# THS3201.net
KiCad netlist of a schematic drawn in Altium Designer
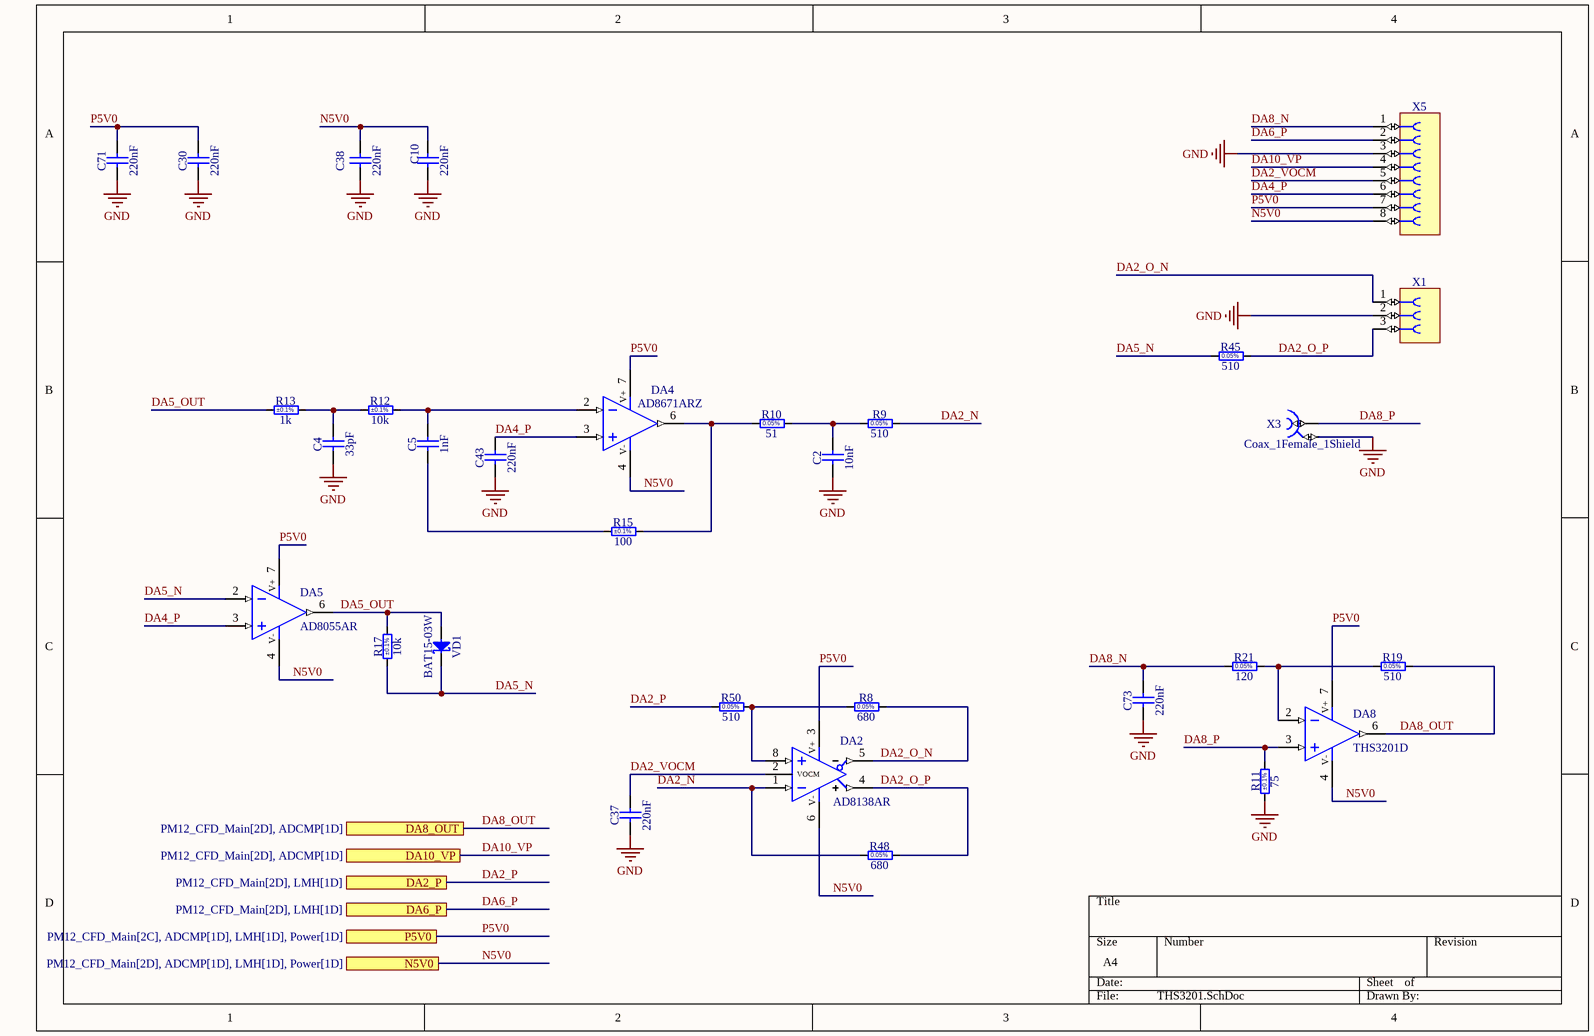
[diagram p0: THS3201.SchDoc]

(export (version "E")
  (design (tool "Eeschema 10.0.6"))
  (components
    (comp (ref "C2")
      (value "10nF")
      (footprint "CAPC2012X135N")
      (description "Non-polarised capacitor")
      (fields
        (field (name "PART NUMBER") "CC0805_10NF_50V_2%_C0G")
        (field (name "VOLTAGE") "50V")
        (field (name "AUTHOR") "CERN DEM HF")
      )
      (libsource (lib "Capacitors") (part "Capacitor - non polarized"))
    )
    (comp (ref "C4")
      (value "33pF")
      (footprint "CAPC2013X115N")
      (description "Non-polarised capacitor")
      (fields
        (field (name "PART NUMBER") "CC0805_33PF_200V_1%_NP0")
        (field (name "VOLTAGE") "200V")
        (field (name "AUTHOR") "CERN DEM HF")
      )
      (libsource (lib "Capacitors") (part "Capacitor - non polarized"))
    )
    (comp (ref "C5")
      (value "1nF")
      (footprint "CAPC2013X100N")
      (description "Non-polarised capacitor")
      (fields
        (field (name "PART NUMBER") "CC0805_1NF_25V_1%_C0G")
        (field (name "VOLTAGE") "25V")
        (field (name "AUTHOR") "CERN DEM JLC")
      )
      (libsource (lib "Capacitors") (part "Capacitor - non polarized"))
    )
    (comp (ref "C10")
      (value "220nF")
      (footprint "CAPC2012X135N")
      (description "Non-polarised capacitor")
      (fields
        (field (name "PART NUMBER") "CC0805_220NF_50V_10%_X7R")
        (field (name "VOLTAGE") "50V")
        (field (name "AUTHOR") "CERN DEM JLC")
      )
      (libsource (lib "Capacitors") (part "Capacitor - non polarized"))
    )
    (comp (ref "C30")
      (value "220nF")
      (footprint "CAPC2012X135N")
      (description "Non-polarised capacitor")
      (fields
        (field (name "PART NUMBER") "CC0805_220NF_50V_10%_X7R")
        (field (name "VOLTAGE") "50V")
        (field (name "AUTHOR") "CERN DEM JLC")
      )
      (libsource (lib "Capacitors") (part "Capacitor - non polarized"))
    )
    (comp (ref "C37")
      (value "220nF")
      (footprint "CAPC2012X135N")
      (description "Non-polarised capacitor")
      (fields
        (field (name "PART NUMBER") "CC0805_220NF_50V_10%_X7R")
        (field (name "VOLTAGE") "50V")
        (field (name "AUTHOR") "CERN DEM JLC")
      )
      (libsource (lib "Capacitors") (part "Capacitor - non polarized"))
    )
    (comp (ref "C38")
      (value "220nF")
      (footprint "CAPC2012X135N")
      (description "Non-polarised capacitor")
      (fields
        (field (name "PART NUMBER") "CC0805_220NF_50V_10%_X7R")
        (field (name "VOLTAGE") "50V")
        (field (name "AUTHOR") "CERN DEM JLC")
      )
      (libsource (lib "Capacitors") (part "Capacitor - non polarized"))
    )
    (comp (ref "C43")
      (value "220nF")
      (footprint "CAPC2012X135N")
      (description "Non-polarised capacitor")
      (fields
        (field (name "PART NUMBER") "CC0805_220NF_50V_10%_X7R")
        (field (name "VOLTAGE") "50V")
        (field (name "AUTHOR") "CERN DEM JLC")
      )
      (libsource (lib "Capacitors") (part "Capacitor - non polarized"))
    )
    (comp (ref "C71")
      (value "220nF")
      (footprint "CAPC2012X135N")
      (description "Non-polarised capacitor")
      (fields
        (field (name "PART NUMBER") "CC0805_220NF_50V_10%_X7R")
        (field (name "VOLTAGE") "50V")
        (field (name "AUTHOR") "CERN DEM JLC")
      )
      (libsource (lib "Capacitors") (part "Capacitor - non polarized"))
    )
    (comp (ref "C73")
      (value "220nF")
      (footprint "CAPC2012X135N")
      (description "Non-polarised capacitor")
      (fields
        (field (name "PART NUMBER") "CC0805_220NF_50V_10%_X7R")
        (field (name "VOLTAGE") "50V")
        (field (name "AUTHOR") "CERN DEM JLC")
      )
      (libsource (lib "Capacitors") (part "Capacitor - non polarized"))
    )
    (comp (ref "DA2")
      (value "AD8138AR")
      (footprint "SOIC127P600X175-8N")
      (description "Differential Amplifier")
      (fields (field (name "MANUFACTURER") "ANALOG DEVICES") (field (name "AUTHOR") "CERN DEM JLC"))
      (libsource (lib "ICs And Semiconductors") (part "Differential Amplifier Type1"))
    )
    (comp (ref "DA4")
      (value "AD8671ARZ")
      (footprint "SOIC127P600X175-8N")
      (description "Operational Amplifier")
      (fields
        (field (name "MANUFACTURER") "ANALOG DEVICES")
        (field (name "MANUFACTURER PART NUMBER") "AD8671AR")
        (field (name "AUTHOR") "CERN DEM JLC")
      )
      (libsource (lib "ICs And Semiconductors") (part "Operational Amplifier Type1"))
    )
    (comp (ref "DA5")
      (value "AD8055AR")
      (footprint "SOIC127P600X175-8N")
      (description "Operational Amplifier")
      (fields (field (name "MANUFACTURER") "ANALOG DEVICES") (field (name "AUTHOR") "CERN DEM HF"))
      (libsource (lib "ICs And Semiconductors") (part "Operational Amplifier Type1"))
    )
    (comp (ref "DA8")
      (value "THS3201D")
      (footprint "SOIC127P600X175-8N")
      (description "Operational Amplifier")
      (fields (field (name "MANUFACTURER") "TEXAS INSTRUMENTS") (field (name "AUTHOR") "CERN DEM HF"))
      (libsource (lib "ICs And Semiconductors") (part "Operational Amplifier Type1"))
    )
    (comp (ref "R8")
      (value "680")
      (footprint "RESC2012X60N")
      (description "Resistor - 0.05%")
      (fields
        (field (name "PART NUMBER") "R0805_680R_0.05%_0.125W_10PPM")
        (field (name "POWER") "0.1W")
        (field (name "AUTHOR") "CERN DEM HF")
      )
      (libsource (lib "Resistors") (part "Resistor - 0.05%"))
    )
    (comp (ref "R9")
      (value "510")
      (footprint "RESC1608X55N")
      (description "Resistor - 0.05%")
      (fields
        (field (name "PART NUMBER") "R0603_510R_0.1%_0.1W_10PPM")
        (field (name "POWER") "0.1W")
        (field (name "AUTHOR") "CERN DEM HF")
      )
      (libsource (lib "Resistors") (part "Resistor - 0.05%"))
    )
    (comp (ref "R10")
      (value "51")
      (footprint "RESC2012X60N")
      (description "Resistor - 0.05%")
      (fields
        (field (name "PART NUMBER") "R0805_51R_0.05%_0.125W_10PPM")
        (field (name "POWER") "0.1W")
        (field (name "AUTHOR") "CERN DEM HF")
      )
      (libsource (lib "Resistors") (part "Resistor - 0.05%"))
    )
    (comp (ref "R11")
      (value "75")
      (footprint "RESC1608X55N")
      (description "Resistor - 0.1%")
      (fields
        (field (name "TOLERANCE") "±0.1%")
        (field (name "PART NUMBER") "R0603_75R_0.1%_0.063W_10PPM")
        (field (name "POWER") "0.063W")
        (field (name "AUTHOR") "CERN DEM JLC")
      )
      (libsource (lib "Resistors") (part "Resistor - 0.1%"))
    )
    (comp (ref "R12")
      (value "10k")
      (footprint "RESC2012X60N")
      (description "Resistor - 0.1%")
      (fields
        (field (name "TOLERANCE") "±0.1%")
        (field (name "PART NUMBER") "R0805_10K_0.1%_0.1W_10PPM")
        (field (name "POWER") "0.1W")
        (field (name "AUTHOR") "CERN DEM JLC")
      )
      (libsource (lib "Resistors") (part "Resistor - 0.1%"))
    )
    (comp (ref "R13")
      (value "1k")
      (footprint "RESC2012X60N")
      (description "Resistor - 0.1%")
      (fields
        (field (name "TOLERANCE") "±0.1%")
        (field (name "PART NUMBER") "R0805_1K_0.1%_0.1W_10PPM")
        (field (name "POWER") "0.1W")
        (field (name "AUTHOR") "CERN DEM JLC")
      )
      (libsource (lib "Resistors") (part "Resistor - 0.1%"))
    )
    (comp (ref "R15")
      (value "100")
      (footprint "RESC2012X60N")
      (description "Resistor - 0.1%")
      (fields
        (field (name "TOLERANCE") "±0.1%")
        (field (name "PART NUMBER") "R0805_100R_0.1%_0.1W_10PPM")
        (field (name "POWER") "0.1W")
        (field (name "AUTHOR") "CERN DEM JLC")
      )
      (libsource (lib "Resistors") (part "Resistor - 0.1%"))
    )
    (comp (ref "R17")
      (value "10k")
      (footprint "RESC2012X60N")
      (description "Resistor - 0.1%")
      (fields
        (field (name "TOLERANCE") "±0.1%")
        (field (name "PART NUMBER") "R0805_10K_0.1%_0.1W_10PPM")
        (field (name "POWER") "0.1W")
        (field (name "AUTHOR") "CERN DEM JLC")
      )
      (libsource (lib "Resistors") (part "Resistor - 0.1%"))
    )
    (comp (ref "R19")
      (value "510")
      (footprint "RESC1608X55N")
      (description "Resistor - 0.05%")
      (fields
        (field (name "PART NUMBER") "R0603_510R_0.1%_0.1W_10PPM")
        (field (name "POWER") "0.1W")
        (field (name "AUTHOR") "CERN DEM HF")
      )
      (libsource (lib "Resistors") (part "Resistor - 0.05%"))
    )
    (comp (ref "R21")
      (value "120")
      (footprint "RESC1608X55N")
      (description "Resistor - 0.05%")
      (fields
        (field (name "PART NUMBER") "R0603_120R_0.05%_0.1W_10PPM")
        (field (name "POWER") "0.1W")
        (field (name "AUTHOR") "CERN DEM HF")
      )
      (libsource (lib "Resistors") (part "Resistor - 0.05%"))
    )
    (comp (ref "R45")
      (value "510")
      (footprint "RESC1608X55N")
      (description "Resistor - 0.05%")
      (fields
        (field (name "PART NUMBER") "R0603_510R_0.1%_0.1W_10PPM")
        (field (name "POWER") "0.1W")
        (field (name "AUTHOR") "CERN DEM HF")
      )
      (libsource (lib "Resistors") (part "Resistor - 0.05%"))
    )
    (comp (ref "R48")
      (value "680")
      (footprint "RESC2012X60N")
      (description "Resistor - 0.05%")
      (fields
        (field (name "PART NUMBER") "R0805_680R_0.05%_0.125W_10PPM")
        (field (name "POWER") "0.1W")
        (field (name "AUTHOR") "CERN DEM HF")
      )
      (libsource (lib "Resistors") (part "Resistor - 0.05%"))
    )
    (comp (ref "R50")
      (value "510")
      (footprint "RESC1608X55N")
      (description "Resistor - 0.05%")
      (fields
        (field (name "PART NUMBER") "R0603_510R_0.1%_0.1W_10PPM")
        (field (name "POWER") "0.1W")
        (field (name "AUTHOR") "CERN DEM HF")
      )
      (libsource (lib "Resistors") (part "Resistor - 0.05%"))
    )
    (comp (ref "VD1")
      (value "BAT15-03W")
      (footprint "SOD2512X110N")
      (description "Schottky Diode")
      (fields
        (field (name "VOLTAGE") "4V")
        (field (name "POWER") "100mA")
        (field (name "AUTHOR") "CERN DEM HF")
      )
      (libsource (lib "ICs And Semiconductors") (part "Diode Schottky"))
    )
    (comp (ref "X1")
      (value "Socket 3")
      (footprint "SAMTEC_CES-103-01-T-S")
      (description "Connector 3 Female")
      (fields
        (field (name "PART NUMBER") "SAMTEC_CES-103-01-L-S")
        (field (name "MANUFACTURER") "SAMTEC")
        (field (name "AUTHOR") "CERN DEM HF")
      )
      (libsource (lib "Connectors") (part "Connector 3 Female"))
    )
    (comp (ref "X3")
      (value "Coax_1Female_1Shield")
      (footprint "SAMTEC_MMCX-J-P-H-ST-TH1")
      (fields
        (field (name "PART NUMBER") "SAMTEC_MMCX-J-P-H-ST-TH1")
        (field (name "MANUFACTURER") "SAMTEC")
        (field (name "MANUFACTURER PART NUMBER") "MMCX-J-P-H-ST-TH1")
        (field (name "AUTHOR") "CERN DEM JLC")
      )
      (libsource (lib "Connectors") (part "Coax_1Female_1Shield"))
    )
    (comp (ref "X5")
      (value "Socket 8")
      (footprint "SAMTEC_CES-108-01-T-S")
      (description "Connector 8 Female")
      (fields
        (field (name "PART NUMBER") "SAMTEC_CES-108-01-L-S")
        (field (name "MANUFACTURER") "SAMTEC")
        (field (name "AUTHOR") "CERN DEM HF")
      )
      (libsource (lib "Connectors") (part "Connector 8 Female"))
    )
  )
  (nets
    (net (code "1") (name "/DA2_N") (class "Default")
      (node (ref "DA2") (pin "1") (pinfunction "IN-_1") (pintype "input"))
      (node (ref "R48") (pin "1") (pinfunction "1_1") (pintype "passive"))
      (node (ref "R9") (pin "2") (pinfunction "2_2") (pintype "passive"))
    )
    (net (code "2") (name "/DA2_O_N") (class "Default")
      (node (ref "DA2") (pin "5") (pinfunction "VOUT-_5") (pintype "output"))
      (node (ref "R8") (pin "2") (pinfunction "2_2") (pintype "passive"))
      (node (ref "X1") (pin "1") (pinfunction "1_1") (pintype "bidirectional"))
    )
    (net (code "3") (name "/DA2_O_P") (class "Default")
      (node (ref "DA2") (pin "4") (pinfunction "VOUT+_4") (pintype "output"))
      (node (ref "R45") (pin "2") (pinfunction "2_2") (pintype "passive"))
      (node (ref "R48") (pin "2") (pinfunction "2_2") (pintype "passive"))
      (node (ref "X1") (pin "3") (pinfunction "3_3") (pintype "bidirectional"))
    )
    (net (code "4") (name "/DA2_P") (class "Default")
      (node (ref "R50") (pin "1") (pinfunction "1_1") (pintype "passive"))
    )
    (net (code "5") (name "/DA2_VOCM") (class "Default")
      (node (ref "C37") (pin "2") (pinfunction "2_2") (pintype "passive"))
      (node (ref "DA2") (pin "2") (pinfunction "VOCM_2") (pintype "passive"))
      (node (ref "X5") (pin "5") (pinfunction "5_5") (pintype "bidirectional"))
    )
    (net (code "6") (name "/DA4_P") (class "Default")
      (node (ref "C43") (pin "2") (pinfunction "2_2") (pintype "passive"))
      (node (ref "DA4") (pin "3") (pinfunction "IN+_3") (pintype "input"))
      (node (ref "DA5") (pin "3") (pinfunction "IN+_3") (pintype "input"))
      (node (ref "X5") (pin "6") (pinfunction "6_6") (pintype "bidirectional"))
    )
    (net (code "7") (name "/DA5_N") (class "Default")
      (node (ref "DA5") (pin "2") (pinfunction "IN-_2") (pintype "input"))
      (node (ref "R17") (pin "1") (pinfunction "1_1") (pintype "passive"))
      (node (ref "R45") (pin "1") (pinfunction "1_1") (pintype "passive"))
      (node (ref "VD1") (pin "1") (pinfunction "C_1") (pintype "passive"))
    )
    (net (code "8") (name "/DA5_OUT") (class "Default")
      (node (ref "DA5") (pin "6") (pinfunction "OUT_6") (pintype "output"))
      (node (ref "R13") (pin "1") (pinfunction "1_1") (pintype "passive"))
      (node (ref "R17") (pin "2") (pinfunction "2_2") (pintype "passive"))
      (node (ref "VD1") (pin "2") (pinfunction "A_2") (pintype "passive"))
    )
    (net (code "9") (name "/DA6_P") (class "Default")
      (node (ref "X5") (pin "2") (pinfunction "2_2") (pintype "bidirectional"))
    )
    (net (code "10") (name "/DA8_N") (class "Default")
      (node (ref "C73") (pin "2") (pinfunction "2_2") (pintype "passive"))
      (node (ref "R21") (pin "1") (pinfunction "1_1") (pintype "passive"))
      (node (ref "X5") (pin "1") (pinfunction "1_1") (pintype "bidirectional"))
    )
    (net (code "11") (name "/DA8_OUT") (class "Default")
      (node (ref "DA8") (pin "6") (pinfunction "OUT_6") (pintype "output"))
      (node (ref "R19") (pin "2") (pinfunction "2_2") (pintype "passive"))
    )
    (net (code "12") (name "/DA8_P") (class "Default")
      (node (ref "DA8") (pin "3") (pinfunction "IN+_3") (pintype "input"))
      (node (ref "R11") (pin "2") (pinfunction "2_2") (pintype "passive"))
      (node (ref "X3") (pin "1") (pinfunction "1_1") (pintype "bidirectional"))
    )
    (net (code "13") (name "/DA10_VP") (class "Default")
      (node (ref "X5") (pin "4") (pinfunction "4_4") (pintype "bidirectional"))
    )
    (net (code "14") (name "/N5V0") (class "Default")
      (node (ref "C10") (pin "2") (pinfunction "2_2") (pintype "passive"))
      (node (ref "C38") (pin "2") (pinfunction "2_2") (pintype "passive"))
      (node (ref "DA2") (pin "6") (pinfunction "V-_6") (pintype "power_in"))
      (node (ref "DA4") (pin "4") (pinfunction "V-_4") (pintype "power_in"))
      (node (ref "DA5") (pin "4") (pinfunction "V-_4") (pintype "power_in"))
      (node (ref "DA8") (pin "4") (pinfunction "V-_4") (pintype "power_in"))
      (node (ref "X5") (pin "8") (pinfunction "8_8") (pintype "bidirectional"))
    )
    (net (code "15") (name "/P5V0") (class "Default")
      (node (ref "C30") (pin "2") (pinfunction "2_2") (pintype "passive"))
      (node (ref "C71") (pin "2") (pinfunction "2_2") (pintype "passive"))
      (node (ref "DA2") (pin "3") (pinfunction "V+_3") (pintype "power_in"))
      (node (ref "DA4") (pin "7") (pinfunction "V+_7") (pintype "power_in"))
      (node (ref "DA5") (pin "7") (pinfunction "V+_7") (pintype "power_in"))
      (node (ref "DA8") (pin "7") (pinfunction "V+_7") (pintype "power_in"))
      (node (ref "X5") (pin "7") (pinfunction "7_7") (pintype "bidirectional"))
    )
    (net (code "16") (name "GND") (class "Default")
      (node (ref "C10") (pin "1") (pinfunction "1_1") (pintype "passive"))
      (node (ref "C2") (pin "1") (pinfunction "1_1") (pintype "passive"))
      (node (ref "C30") (pin "1") (pinfunction "1_1") (pintype "passive"))
      (node (ref "C37") (pin "1") (pinfunction "1_1") (pintype "passive"))
      (node (ref "C38") (pin "1") (pinfunction "1_1") (pintype "passive"))
      (node (ref "C4") (pin "1") (pinfunction "1_1") (pintype "passive"))
      (node (ref "C43") (pin "1") (pinfunction "1_1") (pintype "passive"))
      (node (ref "C71") (pin "1") (pinfunction "1_1") (pintype "passive"))
      (node (ref "C73") (pin "1") (pinfunction "1_1") (pintype "passive"))
      (node (ref "R11") (pin "1") (pinfunction "1_1") (pintype "passive"))
      (node (ref "X1") (pin "2") (pinfunction "2_2") (pintype "bidirectional"))
      (node (ref "X3") (pin "2") (pinfunction "2_2") (pintype "bidirectional"))
      (node (ref "X5") (pin "3") (pinfunction "3_3") (pintype "bidirectional"))
    )
    (net (code "17") (name "Net-(C2-Pad2)") (class "Default")
      (node (ref "C2") (pin "2") (pinfunction "2_2") (pintype "passive"))
      (node (ref "R10") (pin "2") (pinfunction "2_2") (pintype "passive"))
      (node (ref "R9") (pin "1") (pinfunction "1_1") (pintype "passive"))
    )
    (net (code "18") (name "Net-(C4-Pad2)") (class "Default")
      (node (ref "C4") (pin "2") (pinfunction "2_2") (pintype "passive"))
      (node (ref "R12") (pin "1") (pinfunction "1_1") (pintype "passive"))
      (node (ref "R13") (pin "2") (pinfunction "2_2") (pintype "passive"))
    )
    (net (code "19") (name "Net-(C5-Pad1)") (class "Default")
      (node (ref "C5") (pin "1") (pinfunction "1_1") (pintype "passive"))
      (node (ref "R15") (pin "1") (pinfunction "1_1") (pintype "passive"))
    )
    (net (code "20") (name "Net-(DA2-IN+)") (class "Default")
      (node (ref "DA2") (pin "8") (pinfunction "IN+_8") (pintype "input"))
      (node (ref "R50") (pin "2") (pinfunction "2_2") (pintype "passive"))
      (node (ref "R8") (pin "1") (pinfunction "1_1") (pintype "passive"))
    )
    (net (code "21") (name "Net-(DA4-IN-)") (class "Default")
      (node (ref "C5") (pin "2") (pinfunction "2_2") (pintype "passive"))
      (node (ref "DA4") (pin "2") (pinfunction "IN-_2") (pintype "input"))
      (node (ref "R12") (pin "2") (pinfunction "2_2") (pintype "passive"))
    )
    (net (code "22") (name "Net-(DA4-OUT)") (class "Default")
      (node (ref "DA4") (pin "6") (pinfunction "OUT_6") (pintype "output"))
      (node (ref "R10") (pin "1") (pinfunction "1_1") (pintype "passive"))
      (node (ref "R15") (pin "2") (pinfunction "2_2") (pintype "passive"))
    )
    (net (code "23") (name "Net-(DA8-IN-)") (class "Default")
      (node (ref "DA8") (pin "2") (pinfunction "IN-_2") (pintype "input"))
      (node (ref "R19") (pin "1") (pinfunction "1_1") (pintype "passive"))
      (node (ref "R21") (pin "2") (pinfunction "2_2") (pintype "passive"))
    )
  )
)
